# phase.net
KiCad netlist of a schematic drawn in EAGLE
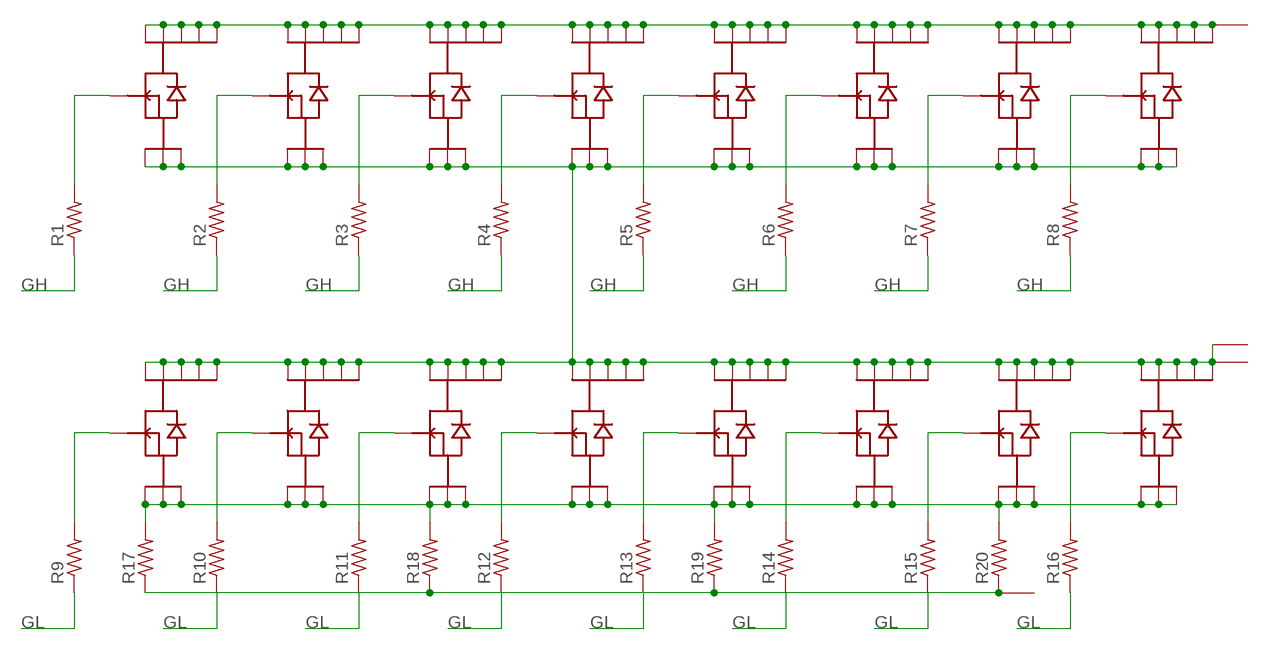
[diagram p0: schematic, sheet 1]

(export (version "E")
  (design (tool "Eeschema 10.0.6"))
  (components
    (comp (ref "R1")
      (value "R-US_R0603")
      (footprint "eagle-import:R0603")
      (libsource (lib "eagle-import") (part "R-US_R0603"))
    )
    (comp (ref "R2")
      (value "R-US_R0603")
      (footprint "eagle-import:R0603")
      (libsource (lib "eagle-import") (part "R-US_R0603"))
    )
    (comp (ref "R3")
      (value "R-US_R0603")
      (footprint "eagle-import:R0603")
      (libsource (lib "eagle-import") (part "R-US_R0603"))
    )
    (comp (ref "R4")
      (value "R-US_R0603")
      (footprint "eagle-import:R0603")
      (libsource (lib "eagle-import") (part "R-US_R0603"))
    )
    (comp (ref "R5")
      (value "R-US_R0603")
      (footprint "eagle-import:R0603")
      (libsource (lib "eagle-import") (part "R-US_R0603"))
    )
    (comp (ref "R6")
      (value "R-US_R0603")
      (footprint "eagle-import:R0603")
      (libsource (lib "eagle-import") (part "R-US_R0603"))
    )
    (comp (ref "R7")
      (value "R-US_R0603")
      (footprint "eagle-import:R0603")
      (libsource (lib "eagle-import") (part "R-US_R0603"))
    )
    (comp (ref "R8")
      (value "R-US_R0603")
      (footprint "eagle-import:R0603")
      (libsource (lib "eagle-import") (part "R-US_R0603"))
    )
    (comp (ref "R9")
      (value "R-US_R0603")
      (footprint "eagle-import:R0603")
      (libsource (lib "eagle-import") (part "R-US_R0603"))
    )
    (comp (ref "R10")
      (value "R-US_R0603")
      (footprint "eagle-import:R0603")
      (libsource (lib "eagle-import") (part "R-US_R0603"))
    )
    (comp (ref "R11")
      (value "R-US_R0603")
      (footprint "eagle-import:R0603")
      (libsource (lib "eagle-import") (part "R-US_R0603"))
    )
    (comp (ref "R12")
      (value "R-US_R0603")
      (footprint "eagle-import:R0603")
      (libsource (lib "eagle-import") (part "R-US_R0603"))
    )
    (comp (ref "R13")
      (value "R-US_R0603")
      (footprint "eagle-import:R0603")
      (libsource (lib "eagle-import") (part "R-US_R0603"))
    )
    (comp (ref "R14")
      (value "R-US_R0603")
      (footprint "eagle-import:R0603")
      (libsource (lib "eagle-import") (part "R-US_R0603"))
    )
    (comp (ref "R15")
      (value "R-US_R0603")
      (footprint "eagle-import:R0603")
      (libsource (lib "eagle-import") (part "R-US_R0603"))
    )
    (comp (ref "R16")
      (value "R-US_R0603")
      (footprint "eagle-import:R0603")
      (libsource (lib "eagle-import") (part "R-US_R0603"))
    )
    (comp (ref "R17")
      (value "R-US_M1206")
      (footprint "eagle-import:M1206")
      (libsource (lib "eagle-import") (part "R-US_M1206"))
    )
    (comp (ref "R18")
      (value "R-US_M1206")
      (footprint "eagle-import:M1206")
      (libsource (lib "eagle-import") (part "R-US_M1206"))
    )
    (comp (ref "R19")
      (value "R-US_M1206")
      (footprint "eagle-import:M1206")
      (libsource (lib "eagle-import") (part "R-US_M1206"))
    )
    (comp (ref "R20")
      (value "R-US_M1206")
      (footprint "eagle-import:M1206")
      (libsource (lib "eagle-import") (part "R-US_M1206"))
    )
    (comp (ref "U$1")
      (value "TPH2R608NH")
      (footprint "eagle-import:SOP-ADVANCE")
      (libsource (lib "eagle-import") (part "TPH2R608NH"))
    )
    (comp (ref "U$2")
      (value "TPH2R608NH")
      (footprint "eagle-import:SOP-ADVANCE")
      (libsource (lib "eagle-import") (part "TPH2R608NH"))
    )
    (comp (ref "U$3")
      (value "TPH2R608NH")
      (footprint "eagle-import:SOP-ADVANCE")
      (libsource (lib "eagle-import") (part "TPH2R608NH"))
    )
    (comp (ref "U$4")
      (value "TPH2R608NH")
      (footprint "eagle-import:SOP-ADVANCE")
      (libsource (lib "eagle-import") (part "TPH2R608NH"))
    )
    (comp (ref "U$5")
      (value "TPH2R608NH")
      (footprint "eagle-import:SOP-ADVANCE")
      (libsource (lib "eagle-import") (part "TPH2R608NH"))
    )
    (comp (ref "U$6")
      (value "TPH2R608NH")
      (footprint "eagle-import:SOP-ADVANCE")
      (libsource (lib "eagle-import") (part "TPH2R608NH"))
    )
    (comp (ref "U$7")
      (value "TPH2R608NH")
      (footprint "eagle-import:SOP-ADVANCE")
      (libsource (lib "eagle-import") (part "TPH2R608NH"))
    )
    (comp (ref "U$8")
      (value "TPH2R608NH")
      (footprint "eagle-import:SOP-ADVANCE")
      (libsource (lib "eagle-import") (part "TPH2R608NH"))
    )
    (comp (ref "U$9")
      (value "TPH2R608NH")
      (footprint "eagle-import:SOP-ADVANCE")
      (libsource (lib "eagle-import") (part "TPH2R608NH"))
    )
    (comp (ref "U$10")
      (value "TPH2R608NH")
      (footprint "eagle-import:SOP-ADVANCE")
      (libsource (lib "eagle-import") (part "TPH2R608NH"))
    )
    (comp (ref "U$11")
      (value "TPH2R608NH")
      (footprint "eagle-import:SOP-ADVANCE")
      (libsource (lib "eagle-import") (part "TPH2R608NH"))
    )
    (comp (ref "U$12")
      (value "TPH2R608NH")
      (footprint "eagle-import:SOP-ADVANCE")
      (libsource (lib "eagle-import") (part "TPH2R608NH"))
    )
    (comp (ref "U$13")
      (value "TPH2R608NH")
      (footprint "eagle-import:SOP-ADVANCE")
      (libsource (lib "eagle-import") (part "TPH2R608NH"))
    )
    (comp (ref "U$14")
      (value "TPH2R608NH")
      (footprint "eagle-import:SOP-ADVANCE")
      (libsource (lib "eagle-import") (part "TPH2R608NH"))
    )
    (comp (ref "U$15")
      (value "TPH2R608NH")
      (footprint "eagle-import:SOP-ADVANCE")
      (libsource (lib "eagle-import") (part "TPH2R608NH"))
    )
    (comp (ref "U$16")
      (value "TPH2R608NH")
      (footprint "eagle-import:SOP-ADVANCE")
      (libsource (lib "eagle-import") (part "TPH2R608NH"))
    )
    (comp (ref "U$17")
      (value "BUSBAR")
      (footprint "eagle-import:BUSBAR")
      (libsource (lib "eagle-import") (part "BUSBAR"))
    )
    (comp (ref "U$18")
      (value "BUSBAR")
      (footprint "eagle-import:BUSBAR")
      (libsource (lib "eagle-import") (part "BUSBAR"))
    )
    (comp (ref "U$19")
      (value "BUSBAR")
      (footprint "eagle-import:BUSBAR")
      (libsource (lib "eagle-import") (part "BUSBAR"))
    )
    (comp (ref "U$20")
      (value "POWERPAD")
      (footprint "eagle-import:POWERPAD")
      (libsource (lib "eagle-import") (part "POWERPAD"))
    )
  )
  (nets
    (net (code "1") (name "/GH") (class "Default")
      (node (ref "R1") (pin "1") (pinfunction "1_1") (pintype "passive"))
      (node (ref "R2") (pin "1") (pinfunction "1_1") (pintype "passive"))
      (node (ref "R3") (pin "1") (pinfunction "1_1") (pintype "passive"))
      (node (ref "R4") (pin "1") (pinfunction "1_1") (pintype "passive"))
      (node (ref "R5") (pin "1") (pinfunction "1_1") (pintype "passive"))
      (node (ref "R6") (pin "1") (pinfunction "1_1") (pintype "passive"))
      (node (ref "R7") (pin "1") (pinfunction "1_1") (pintype "passive"))
      (node (ref "R8") (pin "1") (pinfunction "1_1") (pintype "passive"))
    )
    (net (code "2") (name "/GL") (class "Default")
      (node (ref "R10") (pin "1") (pinfunction "1_1") (pintype "passive"))
      (node (ref "R11") (pin "1") (pinfunction "1_1") (pintype "passive"))
      (node (ref "R12") (pin "1") (pinfunction "1_1") (pintype "passive"))
      (node (ref "R13") (pin "1") (pinfunction "1_1") (pintype "passive"))
      (node (ref "R14") (pin "1") (pinfunction "1_1") (pintype "passive"))
      (node (ref "R15") (pin "1") (pinfunction "1_1") (pintype "passive"))
      (node (ref "R16") (pin "1") (pinfunction "1_1") (pintype "passive"))
      (node (ref "R9") (pin "1") (pinfunction "1_1") (pintype "passive"))
    )
    (net (code "3") (name "Net-(R17-Pad1)") (class "Default")
      (node (ref "R17") (pin "1") (pinfunction "1_1") (pintype "passive"))
      (node (ref "R18") (pin "1") (pinfunction "1_1") (pintype "passive"))
      (node (ref "R19") (pin "1") (pinfunction "1_1") (pintype "passive"))
      (node (ref "R20") (pin "1") (pinfunction "1_1") (pintype "passive"))
      (node (ref "U$19") (pin "P$1") (pinfunction "P$1_P$1") (pintype "bidirectional"))
    )
    (net (code "4") (name "Net-(U$1-D1)") (class "Default")
      (node (ref "U$1") (pin "5") (pinfunction "D1_5") (pintype "bidirectional"))
      (node (ref "U$1") (pin "6") (pinfunction "D2_6") (pintype "bidirectional"))
      (node (ref "U$1") (pin "7") (pinfunction "D3_7") (pintype "bidirectional"))
      (node (ref "U$1") (pin "8") (pinfunction "D4_8") (pintype "bidirectional"))
      (node (ref "U$1") (pin "9") (pinfunction "DTAB_9") (pintype "bidirectional"))
      (node (ref "U$17") (pin "P$1") (pinfunction "P$1_P$1") (pintype "bidirectional"))
      (node (ref "U$2") (pin "5") (pinfunction "D1_5") (pintype "bidirectional"))
      (node (ref "U$2") (pin "6") (pinfunction "D2_6") (pintype "bidirectional"))
      (node (ref "U$2") (pin "7") (pinfunction "D3_7") (pintype "bidirectional"))
      (node (ref "U$2") (pin "8") (pinfunction "D4_8") (pintype "bidirectional"))
      (node (ref "U$2") (pin "9") (pinfunction "DTAB_9") (pintype "bidirectional"))
      (node (ref "U$3") (pin "5") (pinfunction "D1_5") (pintype "bidirectional"))
      (node (ref "U$3") (pin "6") (pinfunction "D2_6") (pintype "bidirectional"))
      (node (ref "U$3") (pin "7") (pinfunction "D3_7") (pintype "bidirectional"))
      (node (ref "U$3") (pin "8") (pinfunction "D4_8") (pintype "bidirectional"))
      (node (ref "U$3") (pin "9") (pinfunction "DTAB_9") (pintype "bidirectional"))
      (node (ref "U$4") (pin "5") (pinfunction "D1_5") (pintype "bidirectional"))
      (node (ref "U$4") (pin "6") (pinfunction "D2_6") (pintype "bidirectional"))
      (node (ref "U$4") (pin "7") (pinfunction "D3_7") (pintype "bidirectional"))
      (node (ref "U$4") (pin "8") (pinfunction "D4_8") (pintype "bidirectional"))
      (node (ref "U$4") (pin "9") (pinfunction "DTAB_9") (pintype "bidirectional"))
      (node (ref "U$5") (pin "5") (pinfunction "D1_5") (pintype "bidirectional"))
      (node (ref "U$5") (pin "6") (pinfunction "D2_6") (pintype "bidirectional"))
      (node (ref "U$5") (pin "7") (pinfunction "D3_7") (pintype "bidirectional"))
      (node (ref "U$5") (pin "8") (pinfunction "D4_8") (pintype "bidirectional"))
      (node (ref "U$5") (pin "9") (pinfunction "DTAB_9") (pintype "bidirectional"))
      (node (ref "U$6") (pin "5") (pinfunction "D1_5") (pintype "bidirectional"))
      (node (ref "U$6") (pin "6") (pinfunction "D2_6") (pintype "bidirectional"))
      (node (ref "U$6") (pin "7") (pinfunction "D3_7") (pintype "bidirectional"))
      (node (ref "U$6") (pin "8") (pinfunction "D4_8") (pintype "bidirectional"))
      (node (ref "U$6") (pin "9") (pinfunction "DTAB_9") (pintype "bidirectional"))
      (node (ref "U$7") (pin "5") (pinfunction "D1_5") (pintype "bidirectional"))
      (node (ref "U$7") (pin "6") (pinfunction "D2_6") (pintype "bidirectional"))
      (node (ref "U$7") (pin "7") (pinfunction "D3_7") (pintype "bidirectional"))
      (node (ref "U$7") (pin "8") (pinfunction "D4_8") (pintype "bidirectional"))
      (node (ref "U$7") (pin "9") (pinfunction "DTAB_9") (pintype "bidirectional"))
      (node (ref "U$8") (pin "5") (pinfunction "D1_5") (pintype "bidirectional"))
      (node (ref "U$8") (pin "6") (pinfunction "D2_6") (pintype "bidirectional"))
      (node (ref "U$8") (pin "7") (pinfunction "D3_7") (pintype "bidirectional"))
      (node (ref "U$8") (pin "8") (pinfunction "D4_8") (pintype "bidirectional"))
      (node (ref "U$8") (pin "9") (pinfunction "DTAB_9") (pintype "bidirectional"))
    )
    (net (code "5") (name "Net-(U$1-G)") (class "Default")
      (node (ref "R1") (pin "2") (pinfunction "2_2") (pintype "passive"))
      (node (ref "U$1") (pin "4") (pinfunction "G_4") (pintype "bidirectional"))
    )
    (net (code "6") (name "Net-(U$1-S1)") (class "Default")
      (node (ref "U$1") (pin "1") (pinfunction "S1_1") (pintype "bidirectional"))
      (node (ref "U$1") (pin "2") (pinfunction "S2_2") (pintype "bidirectional"))
      (node (ref "U$1") (pin "3") (pinfunction "S3_3") (pintype "bidirectional"))
      (node (ref "U$10") (pin "5") (pinfunction "D1_5") (pintype "bidirectional"))
      (node (ref "U$10") (pin "6") (pinfunction "D2_6") (pintype "bidirectional"))
      (node (ref "U$10") (pin "7") (pinfunction "D3_7") (pintype "bidirectional"))
      (node (ref "U$10") (pin "8") (pinfunction "D4_8") (pintype "bidirectional"))
      (node (ref "U$10") (pin "9") (pinfunction "DTAB_9") (pintype "bidirectional"))
      (node (ref "U$11") (pin "5") (pinfunction "D1_5") (pintype "bidirectional"))
      (node (ref "U$11") (pin "6") (pinfunction "D2_6") (pintype "bidirectional"))
      (node (ref "U$11") (pin "7") (pinfunction "D3_7") (pintype "bidirectional"))
      (node (ref "U$11") (pin "8") (pinfunction "D4_8") (pintype "bidirectional"))
      (node (ref "U$11") (pin "9") (pinfunction "DTAB_9") (pintype "bidirectional"))
      (node (ref "U$12") (pin "5") (pinfunction "D1_5") (pintype "bidirectional"))
      (node (ref "U$12") (pin "6") (pinfunction "D2_6") (pintype "bidirectional"))
      (node (ref "U$12") (pin "7") (pinfunction "D3_7") (pintype "bidirectional"))
      (node (ref "U$12") (pin "8") (pinfunction "D4_8") (pintype "bidirectional"))
      (node (ref "U$12") (pin "9") (pinfunction "DTAB_9") (pintype "bidirectional"))
      (node (ref "U$13") (pin "5") (pinfunction "D1_5") (pintype "bidirectional"))
      (node (ref "U$13") (pin "6") (pinfunction "D2_6") (pintype "bidirectional"))
      (node (ref "U$13") (pin "7") (pinfunction "D3_7") (pintype "bidirectional"))
      (node (ref "U$13") (pin "8") (pinfunction "D4_8") (pintype "bidirectional"))
      (node (ref "U$13") (pin "9") (pinfunction "DTAB_9") (pintype "bidirectional"))
      (node (ref "U$14") (pin "5") (pinfunction "D1_5") (pintype "bidirectional"))
      (node (ref "U$14") (pin "6") (pinfunction "D2_6") (pintype "bidirectional"))
      (node (ref "U$14") (pin "7") (pinfunction "D3_7") (pintype "bidirectional"))
      (node (ref "U$14") (pin "8") (pinfunction "D4_8") (pintype "bidirectional"))
      (node (ref "U$14") (pin "9") (pinfunction "DTAB_9") (pintype "bidirectional"))
      (node (ref "U$15") (pin "5") (pinfunction "D1_5") (pintype "bidirectional"))
      (node (ref "U$15") (pin "6") (pinfunction "D2_6") (pintype "bidirectional"))
      (node (ref "U$15") (pin "7") (pinfunction "D3_7") (pintype "bidirectional"))
      (node (ref "U$15") (pin "8") (pinfunction "D4_8") (pintype "bidirectional"))
      (node (ref "U$15") (pin "9") (pinfunction "DTAB_9") (pintype "bidirectional"))
      (node (ref "U$16") (pin "5") (pinfunction "D1_5") (pintype "bidirectional"))
      (node (ref "U$16") (pin "6") (pinfunction "D2_6") (pintype "bidirectional"))
      (node (ref "U$16") (pin "7") (pinfunction "D3_7") (pintype "bidirectional"))
      (node (ref "U$16") (pin "8") (pinfunction "D4_8") (pintype "bidirectional"))
      (node (ref "U$16") (pin "9") (pinfunction "DTAB_9") (pintype "bidirectional"))
      (node (ref "U$18") (pin "P$1") (pinfunction "P$1_P$1") (pintype "bidirectional"))
      (node (ref "U$2") (pin "1") (pinfunction "S1_1") (pintype "bidirectional"))
      (node (ref "U$2") (pin "2") (pinfunction "S2_2") (pintype "bidirectional"))
      (node (ref "U$2") (pin "3") (pinfunction "S3_3") (pintype "bidirectional"))
      (node (ref "U$20") (pin "P$1") (pinfunction "P$1_P$1") (pintype "bidirectional"))
      (node (ref "U$3") (pin "1") (pinfunction "S1_1") (pintype "bidirectional"))
      (node (ref "U$3") (pin "2") (pinfunction "S2_2") (pintype "bidirectional"))
      (node (ref "U$3") (pin "3") (pinfunction "S3_3") (pintype "bidirectional"))
      (node (ref "U$4") (pin "1") (pinfunction "S1_1") (pintype "bidirectional"))
      (node (ref "U$4") (pin "2") (pinfunction "S2_2") (pintype "bidirectional"))
      (node (ref "U$4") (pin "3") (pinfunction "S3_3") (pintype "bidirectional"))
      (node (ref "U$5") (pin "1") (pinfunction "S1_1") (pintype "bidirectional"))
      (node (ref "U$5") (pin "2") (pinfunction "S2_2") (pintype "bidirectional"))
      (node (ref "U$5") (pin "3") (pinfunction "S3_3") (pintype "bidirectional"))
      (node (ref "U$6") (pin "1") (pinfunction "S1_1") (pintype "bidirectional"))
      (node (ref "U$6") (pin "2") (pinfunction "S2_2") (pintype "bidirectional"))
      (node (ref "U$6") (pin "3") (pinfunction "S3_3") (pintype "bidirectional"))
      (node (ref "U$7") (pin "1") (pinfunction "S1_1") (pintype "bidirectional"))
      (node (ref "U$7") (pin "2") (pinfunction "S2_2") (pintype "bidirectional"))
      (node (ref "U$7") (pin "3") (pinfunction "S3_3") (pintype "bidirectional"))
      (node (ref "U$8") (pin "1") (pinfunction "S1_1") (pintype "bidirectional"))
      (node (ref "U$8") (pin "2") (pinfunction "S2_2") (pintype "bidirectional"))
      (node (ref "U$8") (pin "3") (pinfunction "S3_3") (pintype "bidirectional"))
      (node (ref "U$9") (pin "5") (pinfunction "D1_5") (pintype "bidirectional"))
      (node (ref "U$9") (pin "6") (pinfunction "D2_6") (pintype "bidirectional"))
      (node (ref "U$9") (pin "7") (pinfunction "D3_7") (pintype "bidirectional"))
      (node (ref "U$9") (pin "8") (pinfunction "D4_8") (pintype "bidirectional"))
      (node (ref "U$9") (pin "9") (pinfunction "DTAB_9") (pintype "bidirectional"))
    )
    (net (code "7") (name "Net-(U$2-G)") (class "Default")
      (node (ref "R2") (pin "2") (pinfunction "2_2") (pintype "passive"))
      (node (ref "U$2") (pin "4") (pinfunction "G_4") (pintype "bidirectional"))
    )
    (net (code "8") (name "Net-(U$3-G)") (class "Default")
      (node (ref "R3") (pin "2") (pinfunction "2_2") (pintype "passive"))
      (node (ref "U$3") (pin "4") (pinfunction "G_4") (pintype "bidirectional"))
    )
    (net (code "9") (name "Net-(U$4-G)") (class "Default")
      (node (ref "R4") (pin "2") (pinfunction "2_2") (pintype "passive"))
      (node (ref "U$4") (pin "4") (pinfunction "G_4") (pintype "bidirectional"))
    )
    (net (code "10") (name "Net-(U$5-G)") (class "Default")
      (node (ref "R5") (pin "2") (pinfunction "2_2") (pintype "passive"))
      (node (ref "U$5") (pin "4") (pinfunction "G_4") (pintype "bidirectional"))
    )
    (net (code "11") (name "Net-(U$6-G)") (class "Default")
      (node (ref "R6") (pin "2") (pinfunction "2_2") (pintype "passive"))
      (node (ref "U$6") (pin "4") (pinfunction "G_4") (pintype "bidirectional"))
    )
    (net (code "12") (name "Net-(U$7-G)") (class "Default")
      (node (ref "R7") (pin "2") (pinfunction "2_2") (pintype "passive"))
      (node (ref "U$7") (pin "4") (pinfunction "G_4") (pintype "bidirectional"))
    )
    (net (code "13") (name "Net-(U$8-G)") (class "Default")
      (node (ref "R8") (pin "2") (pinfunction "2_2") (pintype "passive"))
      (node (ref "U$8") (pin "4") (pinfunction "G_4") (pintype "bidirectional"))
    )
    (net (code "14") (name "Net-(U$9-G)") (class "Default")
      (node (ref "R9") (pin "2") (pinfunction "2_2") (pintype "passive"))
      (node (ref "U$9") (pin "4") (pinfunction "G_4") (pintype "bidirectional"))
    )
    (net (code "15") (name "Net-(U$10-G)") (class "Default")
      (node (ref "R10") (pin "2") (pinfunction "2_2") (pintype "passive"))
      (node (ref "U$10") (pin "4") (pinfunction "G_4") (pintype "bidirectional"))
    )
    (net (code "16") (name "Net-(U$10-S1)") (class "Default")
      (node (ref "R17") (pin "2") (pinfunction "2_2") (pintype "passive"))
      (node (ref "R18") (pin "2") (pinfunction "2_2") (pintype "passive"))
      (node (ref "R19") (pin "2") (pinfunction "2_2") (pintype "passive"))
      (node (ref "R20") (pin "2") (pinfunction "2_2") (pintype "passive"))
      (node (ref "U$10") (pin "1") (pinfunction "S1_1") (pintype "bidirectional"))
      (node (ref "U$10") (pin "2") (pinfunction "S2_2") (pintype "bidirectional"))
      (node (ref "U$10") (pin "3") (pinfunction "S3_3") (pintype "bidirectional"))
      (node (ref "U$11") (pin "1") (pinfunction "S1_1") (pintype "bidirectional"))
      (node (ref "U$11") (pin "2") (pinfunction "S2_2") (pintype "bidirectional"))
      (node (ref "U$11") (pin "3") (pinfunction "S3_3") (pintype "bidirectional"))
      (node (ref "U$12") (pin "1") (pinfunction "S1_1") (pintype "bidirectional"))
      (node (ref "U$12") (pin "2") (pinfunction "S2_2") (pintype "bidirectional"))
      (node (ref "U$12") (pin "3") (pinfunction "S3_3") (pintype "bidirectional"))
      (node (ref "U$13") (pin "1") (pinfunction "S1_1") (pintype "bidirectional"))
      (node (ref "U$13") (pin "2") (pinfunction "S2_2") (pintype "bidirectional"))
      (node (ref "U$13") (pin "3") (pinfunction "S3_3") (pintype "bidirectional"))
      (node (ref "U$14") (pin "1") (pinfunction "S1_1") (pintype "bidirectional"))
      (node (ref "U$14") (pin "2") (pinfunction "S2_2") (pintype "bidirectional"))
      (node (ref "U$14") (pin "3") (pinfunction "S3_3") (pintype "bidirectional"))
      (node (ref "U$15") (pin "1") (pinfunction "S1_1") (pintype "bidirectional"))
      (node (ref "U$15") (pin "2") (pinfunction "S2_2") (pintype "bidirectional"))
      (node (ref "U$15") (pin "3") (pinfunction "S3_3") (pintype "bidirectional"))
      (node (ref "U$16") (pin "1") (pinfunction "S1_1") (pintype "bidirectional"))
      (node (ref "U$16") (pin "2") (pinfunction "S2_2") (pintype "bidirectional"))
      (node (ref "U$16") (pin "3") (pinfunction "S3_3") (pintype "bidirectional"))
      (node (ref "U$9") (pin "1") (pinfunction "S1_1") (pintype "bidirectional"))
      (node (ref "U$9") (pin "2") (pinfunction "S2_2") (pintype "bidirectional"))
      (node (ref "U$9") (pin "3") (pinfunction "S3_3") (pintype "bidirectional"))
    )
    (net (code "17") (name "Net-(U$11-G)") (class "Default")
      (node (ref "R11") (pin "2") (pinfunction "2_2") (pintype "passive"))
      (node (ref "U$11") (pin "4") (pinfunction "G_4") (pintype "bidirectional"))
    )
    (net (code "18") (name "Net-(U$12-G)") (class "Default")
      (node (ref "R12") (pin "2") (pinfunction "2_2") (pintype "passive"))
      (node (ref "U$12") (pin "4") (pinfunction "G_4") (pintype "bidirectional"))
    )
    (net (code "19") (name "Net-(U$13-G)") (class "Default")
      (node (ref "R13") (pin "2") (pinfunction "2_2") (pintype "passive"))
      (node (ref "U$13") (pin "4") (pinfunction "G_4") (pintype "bidirectional"))
    )
    (net (code "20") (name "Net-(U$14-G)") (class "Default")
      (node (ref "R14") (pin "2") (pinfunction "2_2") (pintype "passive"))
      (node (ref "U$14") (pin "4") (pinfunction "G_4") (pintype "bidirectional"))
    )
    (net (code "21") (name "Net-(U$15-G)") (class "Default")
      (node (ref "R15") (pin "2") (pinfunction "2_2") (pintype "passive"))
      (node (ref "U$15") (pin "4") (pinfunction "G_4") (pintype "bidirectional"))
    )
    (net (code "22") (name "Net-(U$16-G)") (class "Default")
      (node (ref "R16") (pin "2") (pinfunction "2_2") (pintype "passive"))
      (node (ref "U$16") (pin "4") (pinfunction "G_4") (pintype "bidirectional"))
    )
  )
)
